# fat41.net
KiCad netlist of a schematic drawn in Altium Designer
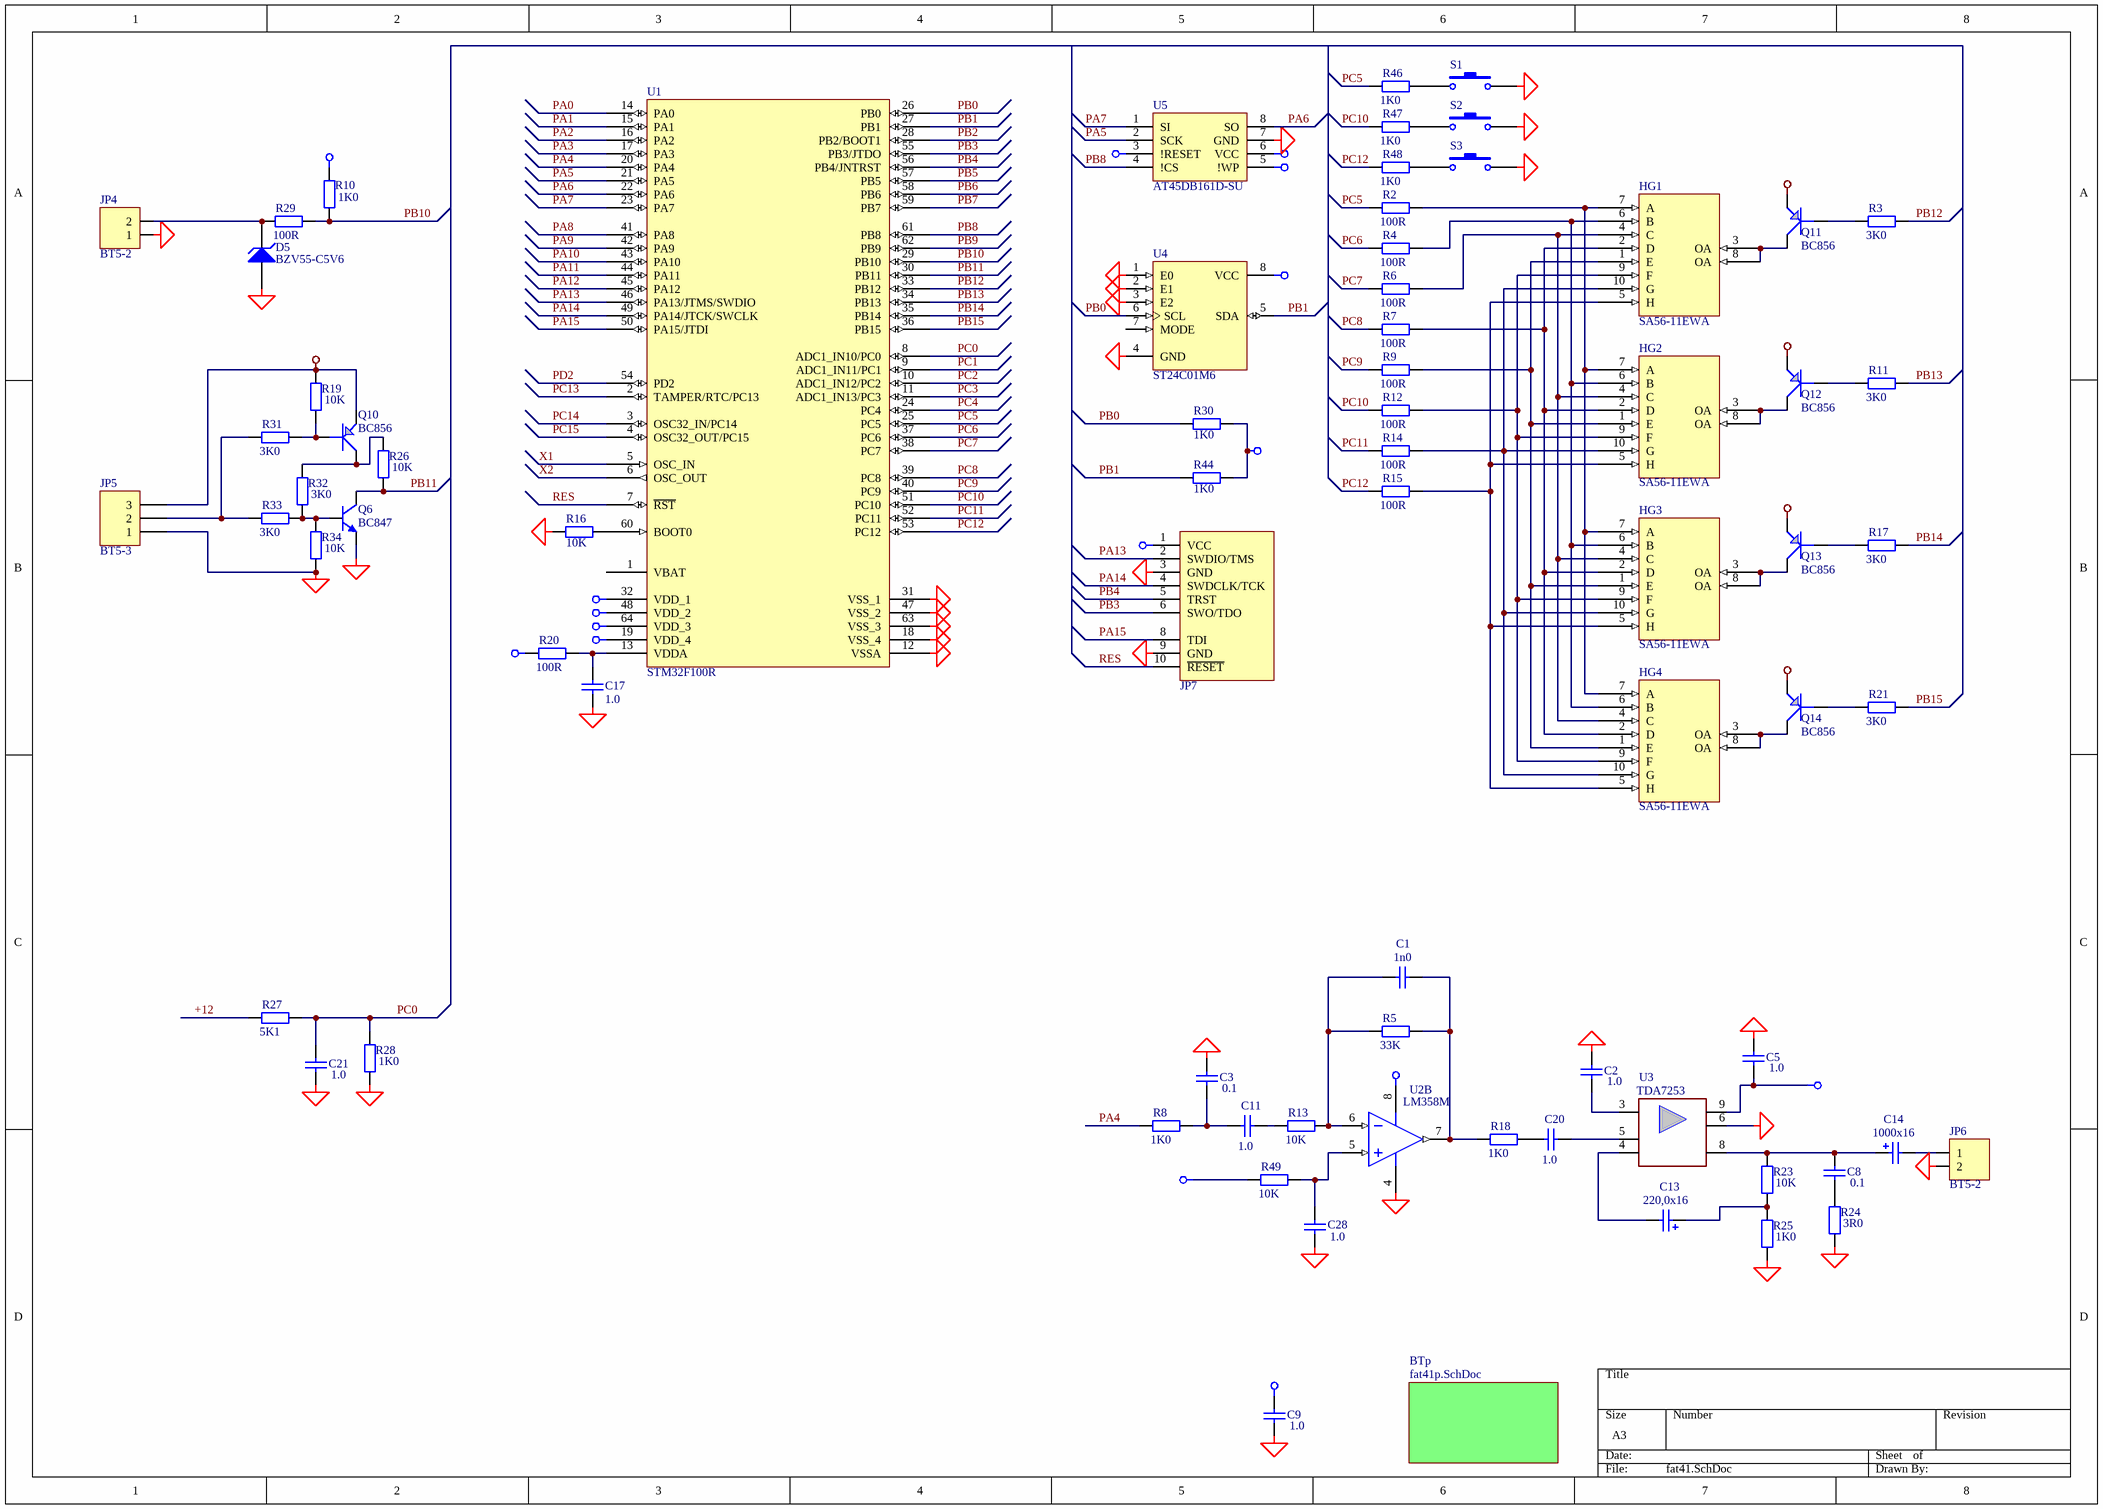
[diagram p0: fat41.SchDoc]

(export (version "E")
  (design (tool "Eeschema 10.0.6"))
  (components
    (comp (ref "C1")
      (value "1n0")
      (footprint "_1206")
      (description "Capacitor (Semiconductor SIM Model)")
      (fields (field (name "MANUFACTURER") "Generic Components") (field (name "PUBLISHER") "Altium Limited"))
      (libsource (lib "Miscellaneous Devices") (part "Cap Semi"))
    )
    (comp (ref "C2")
      (value "1.0")
      (footprint "C3216-1206")
      (description "Capacitor (Semiconductor SIM Model)")
      (fields (field (name "MANUFACTURER") "Generic Components") (field (name "PUBLISHER") "Altium Limited"))
      (libsource (lib "Miscellaneous Devices") (part "Cap Semi"))
    )
    (comp (ref "C3")
      (value "0.1")
      (footprint "_1206")
      (description "Capacitor (Semiconductor SIM Model)")
      (fields (field (name "MANUFACTURER") "Generic Components") (field (name "PUBLISHER") "Altium Limited"))
      (libsource (lib "") (part "Cap Semi_1"))
    )
    (comp (ref "C5")
      (value "1.0")
      (footprint "C3216-1206")
      (description "Capacitor (Semiconductor SIM Model)")
      (fields (field (name "MANUFACTURER") "Generic Components") (field (name "PUBLISHER") "Altium Limited"))
      (libsource (lib "Miscellaneous Devices") (part "Cap Semi"))
    )
    (comp (ref "C8")
      (value "0.1")
      (footprint "C3216-1206")
      (description "Capacitor (Semiconductor SIM Model)")
      (fields (field (name "MANUFACTURER") "Generic Components") (field (name "PUBLISHER") "Altium Limited"))
      (libsource (lib "Miscellaneous Devices") (part "Cap Semi"))
    )
    (comp (ref "C9")
      (value "1.0")
      (footprint "C3216-1206")
      (description "Capacitor (Semiconductor SIM Model)")
      (fields (field (name "MANUFACTURER") "Generic Components") (field (name "PUBLISHER") "Altium Limited"))
      (libsource (lib "Miscellaneous Devices") (part "Cap Semi"))
    )
    (comp (ref "C11")
      (value "1.0")
      (footprint "_1206")
      (description "Capacitor (Semiconductor SIM Model)")
      (fields (field (name "MANUFACTURER") "Generic Components") (field (name "PUBLISHER") "Altium Limited"))
      (libsource (lib "Miscellaneous Devices") (part "Cap Semi"))
    )
    (comp (ref "C13")
      (value "220,0x16")
      (footprint "el3")
      (description "Polarized Capacitor (Radial)")
      (fields (field (name "MANUFACTURER") "Generic Components") (field (name "PUBLISHER") "Altium Limited"))
      (libsource (lib "PAL") (part "Cap Pol1"))
    )
    (comp (ref "C14")
      (value "1000x16")
      (footprint "el5")
      (description "Polarized Capacitor (Radial)")
      (fields (field (name "MANUFACTURER") "Generic Components") (field (name "PUBLISHER") "Altium Limited"))
      (libsource (lib "PAL") (part "Cap Pol1"))
    )
    (comp (ref "C17")
      (value "1.0")
      (footprint "_1206")
      (description "Capacitor (Semiconductor SIM Model)")
      (fields (field (name "MANUFACTURER") "Generic Components") (field (name "PUBLISHER") "Altium Limited"))
      (libsource (lib "") (part "Cap Semi_1"))
    )
    (comp (ref "C20")
      (value "1.0")
      (footprint "_1206")
      (description "Capacitor (Semiconductor SIM Model)")
      (fields (field (name "MANUFACTURER") "Generic Components") (field (name "PUBLISHER") "Altium Limited"))
      (libsource (lib "Miscellaneous Devices") (part "Cap Semi"))
    )
    (comp (ref "C21")
      (value "1.0")
      (footprint "_1206")
      (description "Capacitor (Semiconductor SIM Model)")
      (fields (field (name "MANUFACTURER") "Generic Components") (field (name "PUBLISHER") "Altium Limited"))
      (libsource (lib "Miscellaneous Devices") (part "Cap Semi"))
    )
    (comp (ref "C28")
      (value "1.0")
      (footprint "_1206")
      (description "Capacitor (Semiconductor SIM Model)")
      (fields (field (name "MANUFACTURER") "Generic Components") (field (name "PUBLISHER") "Altium Limited"))
      (libsource (lib "") (part "Cap Semi_1"))
    )
    (comp (ref "D5")
      (value "BZV55-C5V6")
      (footprint "_1206d")
      (description "Zener Diode")
      (fields (field (name "MANUFACTURER") "Generic Components") (field (name "PUBLISHER") "Altium Limited"))
      (libsource (lib "Miscellaneous Devices") (part "D Zener"))
    )
    (comp (ref "HG1") (value "SA56-11EWA") (footprint "DIP10") (libsource (lib "PAL") (part "SA05")))
    (comp (ref "HG2") (value "SA56-11EWA") (footprint "DIP10") (libsource (lib "PAL") (part "SA05")))
    (comp (ref "HG3") (value "SA56-11EWA") (footprint "DIP10") (libsource (lib "PAL") (part "SA05")))
    (comp (ref "HG4") (value "SA56-11EWA") (footprint "DIP10") (libsource (lib "PAL") (part "SA05")))
    (comp (ref "JP4")
      (value "BT5-2")
      (footprint "BT5-2-1")
      (description "Header, 3-Pin")
      (fields (field (name "MANUFACTURER") "Generic Components") (field (name "PUBLISHER") "Altium Limited"))
      (libsource (lib "") (part "BT5-2_1"))
    )
    (comp (ref "JP5")
      (value "BT5-3")
      (footprint "BT5-3")
      (description "Header, 3-Pin")
      (fields (field (name "MANUFACTURER") "Generic Components") (field (name "PUBLISHER") "Altium Limited"))
      (libsource (lib "Miscellaneous Connectors") (part "Header 3"))
    )
    (comp (ref "JP6")
      (value "BT5-2")
      (footprint "BT5-2-1")
      (description "Header, 3-Pin")
      (fields (field (name "MANUFACTURER") "Generic Components") (field (name "PUBLISHER") "Altium Limited"))
      (libsource (lib "PAL") (part "BT5-2"))
    )
    (comp (ref "JP7")
      (value "CORTEX_DEBUG_CONNECTOR_PAL")
      (footprint "CORTEX_DEBUG_CONNECTOR")
      (libsource (lib "PAL") (part "CORTEX_DEBUG_CONNECTOR_PAL"))
    )
    (comp (ref "Q6")
      (value "BC847")
      (footprint "SO-G3")
      (description "General Purpose Transistor NPN Silicon")
      (fields (field (name "MANUFACTURER") "Motorola") (field (name "PUBLISHER") "Altium Limited"))
      (libsource (lib "PAL") (part "BC847ALT1"))
    )
    (comp (ref "Q10") (value "BC856") (footprint "SO-G3") (libsource (lib "MAIN") (part "GT109")))
    (comp (ref "Q11") (value "BC856") (footprint "SO-G3") (libsource (lib "MAIN") (part "GT109")))
    (comp (ref "Q12") (value "BC856") (footprint "SO-G3") (libsource (lib "MAIN") (part "GT109")))
    (comp (ref "Q13") (value "BC856") (footprint "SO-G3") (libsource (lib "MAIN") (part "GT109")))
    (comp (ref "Q14") (value "BC856") (footprint "SO-G3") (libsource (lib "MAIN") (part "GT109")))
    (comp (ref "R2")
      (value "100R")
      (footprint "_1206")
      (description "Resistor")
      (fields (field (name "MANUFACTURER") "Generic Components") (field (name "PUBLISHER") "Altium Limited"))
      (libsource (lib "PAL") (part "RES"))
    )
    (comp (ref "R3")
      (value "3K0")
      (footprint "_1206")
      (description "Resistor")
      (fields (field (name "MANUFACTURER") "Generic Components") (field (name "PUBLISHER") "Altium Limited"))
      (libsource (lib "PAL") (part "RES"))
    )
    (comp (ref "R4")
      (value "100R")
      (footprint "_1206")
      (description "Resistor")
      (fields (field (name "MANUFACTURER") "Generic Components") (field (name "PUBLISHER") "Altium Limited"))
      (libsource (lib "PAL") (part "RES"))
    )
    (comp (ref "R5")
      (value "33K")
      (footprint "_1206")
      (description "Resistor")
      (fields (field (name "MANUFACTURER") "Generic Components") (field (name "PUBLISHER") "Altium Limited"))
      (libsource (lib "") (part "Res2_1"))
    )
    (comp (ref "R6")
      (value "100R")
      (footprint "_1206")
      (description "Resistor")
      (fields (field (name "MANUFACTURER") "Generic Components") (field (name "PUBLISHER") "Altium Limited"))
      (libsource (lib "PAL") (part "RES"))
    )
    (comp (ref "R7")
      (value "100R")
      (footprint "_1206")
      (description "Resistor")
      (fields (field (name "MANUFACTURER") "Generic Components") (field (name "PUBLISHER") "Altium Limited"))
      (libsource (lib "PAL") (part "RES"))
    )
    (comp (ref "R8")
      (value "1K0")
      (footprint "_1206")
      (description "Resistor")
      (fields (field (name "MANUFACTURER") "Generic Components") (field (name "PUBLISHER") "Altium Limited"))
      (libsource (lib "") (part "Res2_1"))
    )
    (comp (ref "R9")
      (value "100R")
      (footprint "_1206")
      (description "Resistor")
      (fields (field (name "MANUFACTURER") "Generic Components") (field (name "PUBLISHER") "Altium Limited"))
      (libsource (lib "PAL") (part "RES"))
    )
    (comp (ref "R10")
      (value "1K0")
      (footprint "_1206")
      (description "Resistor")
      (fields (field (name "MANUFACTURER") "Generic Components") (field (name "PUBLISHER") "Altium Limited"))
      (libsource (lib "") (part "Res2_2"))
    )
    (comp (ref "R11")
      (value "3K0")
      (footprint "_1206")
      (description "Resistor")
      (fields (field (name "MANUFACTURER") "Generic Components") (field (name "PUBLISHER") "Altium Limited"))
      (libsource (lib "PAL") (part "RES"))
    )
    (comp (ref "R12")
      (value "100R")
      (footprint "_1206")
      (description "Resistor")
      (fields (field (name "MANUFACTURER") "Generic Components") (field (name "PUBLISHER") "Altium Limited"))
      (libsource (lib "PAL") (part "RES"))
    )
    (comp (ref "R13")
      (value "10K")
      (footprint "_1206")
      (description "Resistor")
      (fields (field (name "MANUFACTURER") "Generic Components") (field (name "PUBLISHER") "Altium Limited"))
      (libsource (lib "") (part "Res2_1"))
    )
    (comp (ref "R14")
      (value "100R")
      (footprint "_1206")
      (description "Resistor")
      (fields (field (name "MANUFACTURER") "Generic Components") (field (name "PUBLISHER") "Altium Limited"))
      (libsource (lib "PAL") (part "RES"))
    )
    (comp (ref "R15")
      (value "100R")
      (footprint "_1206")
      (description "Resistor")
      (fields (field (name "MANUFACTURER") "Generic Components") (field (name "PUBLISHER") "Altium Limited"))
      (libsource (lib "PAL") (part "RES"))
    )
    (comp (ref "R16")
      (value "10K")
      (footprint "_1206")
      (description "Resistor")
      (fields (field (name "MANUFACTURER") "Generic Components") (field (name "PUBLISHER") "Altium Limited"))
      (libsource (lib "PAL") (part "RES"))
    )
    (comp (ref "R17")
      (value "3K0")
      (footprint "_1206")
      (description "Resistor")
      (fields (field (name "MANUFACTURER") "Generic Components") (field (name "PUBLISHER") "Altium Limited"))
      (libsource (lib "PAL") (part "RES"))
    )
    (comp (ref "R18")
      (value "1K0")
      (footprint "_1206")
      (description "Resistor")
      (fields (field (name "MANUFACTURER") "Generic Components") (field (name "PUBLISHER") "Altium Limited"))
      (libsource (lib "") (part "Res2_3"))
    )
    (comp (ref "R19")
      (value "10K")
      (footprint "_1206")
      (description "Resistor")
      (fields (field (name "MANUFACTURER") "Generic Components") (field (name "PUBLISHER") "Altium Limited"))
      (libsource (lib "PAL") (part "RES"))
    )
    (comp (ref "R20")
      (value "100R")
      (footprint "_1206")
      (description "Resistor")
      (fields (field (name "MANUFACTURER") "Generic Components") (field (name "PUBLISHER") "Altium Limited"))
      (libsource (lib "Miscellaneous Devices") (part "Res2"))
    )
    (comp (ref "R21")
      (value "3K0")
      (footprint "_1206")
      (description "Resistor")
      (fields (field (name "MANUFACTURER") "Generic Components") (field (name "PUBLISHER") "Altium Limited"))
      (libsource (lib "PAL") (part "RES"))
    )
    (comp (ref "R23")
      (value "10K")
      (footprint "_1206")
      (description "Resistor")
      (fields (field (name "MANUFACTURER") "Generic Components") (field (name "PUBLISHER") "Altium Limited"))
      (libsource (lib "") (part "RES_1"))
    )
    (comp (ref "R24")
      (value "3R0")
      (footprint "_1206")
      (description "Resistor")
      (fields (field (name "MANUFACTURER") "Generic Components") (field (name "PUBLISHER") "Altium Limited"))
      (libsource (lib "") (part "RES_1"))
    )
    (comp (ref "R25")
      (value "1K0")
      (footprint "_1206")
      (description "Resistor")
      (fields (field (name "MANUFACTURER") "Generic Components") (field (name "PUBLISHER") "Altium Limited"))
      (libsource (lib "") (part "RES_1"))
    )
    (comp (ref "R26")
      (value "10K")
      (footprint "_1206")
      (description "Resistor")
      (fields (field (name "MANUFACTURER") "Generic Components") (field (name "PUBLISHER") "Altium Limited"))
      (libsource (lib "") (part "RES_2"))
    )
    (comp (ref "R27")
      (value "5K1")
      (footprint "_1206")
      (description "Resistor")
      (fields (field (name "MANUFACTURER") "Generic Components") (field (name "PUBLISHER") "Altium Limited"))
      (libsource (lib "Miscellaneous Devices") (part "Res2"))
    )
    (comp (ref "R28")
      (value "1K0")
      (footprint "_1206")
      (description "Resistor")
      (fields (field (name "MANUFACTURER") "Generic Components") (field (name "PUBLISHER") "Altium Limited"))
      (libsource (lib "") (part "Res2_2"))
    )
    (comp (ref "R29")
      (value "100R")
      (footprint "_1206")
      (description "Resistor")
      (fields (field (name "MANUFACTURER") "Generic Components") (field (name "PUBLISHER") "Altium Limited"))
      (libsource (lib "Miscellaneous Devices") (part "Res2"))
    )
    (comp (ref "R30")
      (value "1K0")
      (footprint "_1206")
      (description "Resistor")
      (fields (field (name "MANUFACTURER") "Generic Components") (field (name "PUBLISHER") "Altium Limited"))
      (libsource (lib "PAL") (part "RES"))
    )
    (comp (ref "R31")
      (value "3K0")
      (footprint "_1206")
      (description "Resistor")
      (fields (field (name "MANUFACTURER") "Generic Components") (field (name "PUBLISHER") "Altium Limited"))
      (libsource (lib "Miscellaneous Devices") (part "Res2"))
    )
    (comp (ref "R32")
      (value "3K0")
      (footprint "_1206")
      (description "Resistor")
      (fields (field (name "MANUFACTURER") "Generic Components") (field (name "PUBLISHER") "Altium Limited"))
      (libsource (lib "") (part "Res2_2"))
    )
    (comp (ref "R33")
      (value "3K0")
      (footprint "_1206")
      (description "Resistor")
      (fields (field (name "MANUFACTURER") "Generic Components") (field (name "PUBLISHER") "Altium Limited"))
      (libsource (lib "Miscellaneous Devices") (part "Res2"))
    )
    (comp (ref "R34")
      (value "10K")
      (footprint "_1206")
      (description "Resistor")
      (fields (field (name "MANUFACTURER") "Generic Components") (field (name "PUBLISHER") "Altium Limited"))
      (libsource (lib "") (part "Res2_1"))
    )
    (comp (ref "R44")
      (value "1K0")
      (footprint "_1206")
      (description "Resistor")
      (fields (field (name "MANUFACTURER") "Generic Components") (field (name "PUBLISHER") "Altium Limited"))
      (libsource (lib "PAL") (part "RES"))
    )
    (comp (ref "R46")
      (value "1K0")
      (footprint "_1206")
      (description "Resistor")
      (fields (field (name "MANUFACTURER") "Generic Components") (field (name "PUBLISHER") "Altium Limited"))
      (libsource (lib "PAL") (part "RES"))
    )
    (comp (ref "R47")
      (value "1K0")
      (footprint "_1206")
      (description "Resistor")
      (fields (field (name "MANUFACTURER") "Generic Components") (field (name "PUBLISHER") "Altium Limited"))
      (libsource (lib "PAL") (part "RES"))
    )
    (comp (ref "R48")
      (value "1K0")
      (footprint "_1206")
      (description "Resistor")
      (fields (field (name "MANUFACTURER") "Generic Components") (field (name "PUBLISHER") "Altium Limited"))
      (libsource (lib "PAL") (part "RES"))
    )
    (comp (ref "R49")
      (value "10K")
      (footprint "_1206")
      (description "Resistor")
      (fields (field (name "MANUFACTURER") "Generic Components") (field (name "PUBLISHER") "Altium Limited"))
      (libsource (lib "") (part "Res2_1"))
    )
    (comp (ref "S1")
      (value "SWT-6")
      (footprint "SWT-6-9")
      (description "Switch")
      (fields (field (name "MANUFACTURER") "Generic Components") (field (name "PUBLISHER") "Altium Limited"))
      (libsource (lib "PAL") (part "SWT-6"))
    )
    (comp (ref "S2")
      (value "SWT-6")
      (footprint "SWT-6-9")
      (description "Switch")
      (fields (field (name "MANUFACTURER") "Generic Components") (field (name "PUBLISHER") "Altium Limited"))
      (libsource (lib "PAL") (part "SWT-6"))
    )
    (comp (ref "S3")
      (value "SWT-6")
      (footprint "SWT-6-9")
      (description "Switch")
      (fields (field (name "MANUFACTURER") "Generic Components") (field (name "PUBLISHER") "Altium Limited"))
      (libsource (lib "PAL") (part "SWT-6"))
    )
    (comp (ref "U1")
      (value "STM32F100R")
      (footprint "F-QFP10X10-G64/N")
      (description "STM32 ARM-based 32-bit MCU with 64 Kbytes Flash, 64-pin LQFP, Industrial Temperature")
      (fields (field (name "PUBLISHER") "*"))
      (libsource (lib "PAL") (part "STM32F100R"))
    )
    (comp (ref "U2")
      (value "LM358M")
      (footprint "SO-G8")
      (description "Low-Power Dual Operational Amplifier")
      (fields
        (field (name "MANUFACTURER") "National Semiconductor")
        (field (name "PUBLISHER") "Altium Limited")
      )
      (libsource (lib "NSC Operational Amplifier") (part "LM358M"))
    )
    (comp (ref "U3") (value "TDA7253") (footprint "Clipwatt11") (libsource (lib "PAL") (part "TDA7253")))
    (comp (ref "U4")
      (value "ST24C01M6")
      (footprint "SO-G8")
      (description "Serial 1K (128 x 8) EEPROM")
      (fields (field (name "MANUFACTURER") "ST-Microelectronics") (field (name "PUBLISHER") "Altium Limited"))
      (libsource (lib "ST Memory EEPROM Serial") (part "ST24C01M6"))
    )
    (comp (ref "U5")
      (value "AT45DB161D-SU")
      (footprint "at45w")
      (libsource (lib "igorenja") (part "AT45DB161D-SU"))
    )
  )
  (nets
    (net (code "1") (name "+3v3") (class "Default")
      (node (ref "C9") (pin "2") (pinfunction "2_2") (pintype "passive"))
      (node (ref "JP7") (pin "1") (pinfunction "VCC_1") (pintype "passive"))
      (node (ref "Q11") (pin "2") (pinfunction "E_2") (pintype "passive"))
      (node (ref "Q12") (pin "2") (pinfunction "E_2") (pintype "passive"))
      (node (ref "Q13") (pin "2") (pinfunction "E_2") (pintype "passive"))
      (node (ref "Q14") (pin "2") (pinfunction "E_2") (pintype "passive"))
      (node (ref "R10") (pin "1") (pinfunction "1_1") (pintype "passive"))
      (node (ref "R20") (pin "2") (pinfunction "2_2") (pintype "passive"))
      (node (ref "R30") (pin "2") (pinfunction "2_2") (pintype "passive"))
      (node (ref "R44") (pin "2") (pinfunction "2_2") (pintype "passive"))
      (node (ref "R49") (pin "2") (pinfunction "2_2") (pintype "passive"))
      (node (ref "U1") (pin "19") (pinfunction "VDD_4_19") (pintype "power_in"))
      (node (ref "U1") (pin "32") (pinfunction "VDD_1_32") (pintype "power_in"))
      (node (ref "U1") (pin "48") (pinfunction "VDD_2_48") (pintype "power_in"))
      (node (ref "U1") (pin "64") (pinfunction "VDD_3_64") (pintype "power_in"))
      (node (ref "U4") (pin "8") (pinfunction "VCC_8") (pintype "power_in"))
      (node (ref "U5") (pin "3") (pinfunction "!RESET_3") (pintype "passive"))
      (node (ref "U5") (pin "5") (pinfunction "!WP_5") (pintype "passive"))
      (node (ref "U5") (pin "6") (pinfunction "VCC_6") (pintype "passive"))
    )
    (net (code "2") (name "+12v") (class "Default")
      (node (ref "C5") (pin "1") (pinfunction "1_1") (pintype "passive"))
      (node (ref "JP5") (pin "3") (pinfunction "3_3") (pintype "passive"))
      (node (ref "Q10") (pin "2") (pinfunction "E_2") (pintype "passive"))
      (node (ref "R19") (pin "2") (pinfunction "2_2") (pintype "passive"))
      (node (ref "U2") (pin "8") (pinfunction "V+_8") (pintype "power_in"))
      (node (ref "U3") (pin "9") (pintype "passive"))
    )
    (net (code "3") (name "/+12") (class "Default")
      (node (ref "R27") (pin "2") (pinfunction "2_2") (pintype "passive"))
    )
    (net (code "4") (name "/PA0") (class "Default")
      (node (ref "U1") (pin "14") (pinfunction "PA0_14") (pintype "bidirectional"))
    )
    (net (code "5") (name "/PA1") (class "Default")
      (node (ref "U1") (pin "15") (pinfunction "PA1_15") (pintype "bidirectional"))
    )
    (net (code "6") (name "/PA2") (class "Default")
      (node (ref "U1") (pin "16") (pinfunction "PA2_16") (pintype "bidirectional"))
    )
    (net (code "7") (name "/PA3") (class "Default")
      (node (ref "U1") (pin "17") (pinfunction "PA3_17") (pintype "bidirectional"))
    )
    (net (code "8") (name "/PA4") (class "Default")
      (node (ref "R8") (pin "2") (pinfunction "2_2") (pintype "passive"))
      (node (ref "U1") (pin "20") (pinfunction "PA4_20") (pintype "bidirectional"))
    )
    (net (code "9") (name "/PA5") (class "Default")
      (node (ref "U1") (pin "21") (pinfunction "PA5_21") (pintype "bidirectional"))
      (node (ref "U5") (pin "2") (pinfunction "SCK_2") (pintype "passive"))
    )
    (net (code "10") (name "/PA6") (class "Default")
      (node (ref "U1") (pin "22") (pinfunction "PA6_22") (pintype "bidirectional"))
      (node (ref "U5") (pin "8") (pinfunction "SO_8") (pintype "passive"))
    )
    (net (code "11") (name "/PA7") (class "Default")
      (node (ref "U1") (pin "23") (pinfunction "PA7_23") (pintype "bidirectional"))
      (node (ref "U5") (pin "1") (pinfunction "SI_1") (pintype "passive"))
    )
    (net (code "12") (name "/PA8") (class "Default")
      (node (ref "U1") (pin "41") (pinfunction "PA8_41") (pintype "bidirectional"))
    )
    (net (code "13") (name "/PA9") (class "Default")
      (node (ref "U1") (pin "42") (pinfunction "PA9_42") (pintype "bidirectional"))
    )
    (net (code "14") (name "/PA10") (class "Default")
      (node (ref "U1") (pin "43") (pinfunction "PA10_43") (pintype "bidirectional"))
    )
    (net (code "15") (name "/PA11") (class "Default")
      (node (ref "U1") (pin "44") (pinfunction "PA11_44") (pintype "bidirectional"))
    )
    (net (code "16") (name "/PA12") (class "Default")
      (node (ref "U1") (pin "45") (pinfunction "PA12_45") (pintype "bidirectional"))
    )
    (net (code "17") (name "/PA13") (class "Default")
      (node (ref "JP7") (pin "2") (pinfunction "SWDIO/TMS_2") (pintype "passive"))
      (node (ref "U1") (pin "46") (pinfunction "PA13/JTMS/SWDIO_46") (pintype "bidirectional"))
    )
    (net (code "18") (name "/PA14") (class "Default")
      (node (ref "JP7") (pin "4") (pinfunction "SWDCLK/TCK_4") (pintype "passive"))
      (node (ref "U1") (pin "49") (pinfunction "PA14/JTCK/SWCLK_49") (pintype "bidirectional"))
    )
    (net (code "19") (name "/PA15") (class "Default")
      (node (ref "JP7") (pin "8") (pinfunction "TDI_8") (pintype "passive"))
      (node (ref "U1") (pin "50") (pinfunction "PA15/JTDI_50") (pintype "bidirectional"))
    )
    (net (code "20") (name "/PB0") (class "Default")
      (node (ref "R30") (pin "1") (pinfunction "1_1") (pintype "passive"))
      (node (ref "U1") (pin "26") (pinfunction "PB0_26") (pintype "bidirectional"))
      (node (ref "U4") (pin "6") (pinfunction "SCL_6") (pintype "input"))
    )
    (net (code "21") (name "/PB1") (class "Default")
      (node (ref "R44") (pin "1") (pinfunction "1_1") (pintype "passive"))
      (node (ref "U1") (pin "27") (pinfunction "PB1_27") (pintype "bidirectional"))
      (node (ref "U4") (pin "5") (pinfunction "SDA_5") (pintype "bidirectional"))
    )
    (net (code "22") (name "/PB2") (class "Default")
      (node (ref "U1") (pin "28") (pinfunction "PB2/BOOT1_28") (pintype "bidirectional"))
    )
    (net (code "23") (name "/PB3") (class "Default")
      (node (ref "JP7") (pin "6") (pinfunction "SWO/TDO_6") (pintype "passive"))
      (node (ref "U1") (pin "55") (pinfunction "PB3/JTDO_55") (pintype "bidirectional"))
    )
    (net (code "24") (name "/PB4") (class "Default")
      (node (ref "JP7") (pin "5") (pinfunction "TRST_5") (pintype "passive"))
      (node (ref "U1") (pin "56") (pinfunction "PB4/JNTRST_56") (pintype "bidirectional"))
    )
    (net (code "25") (name "/PB5") (class "Default")
      (node (ref "U1") (pin "57") (pinfunction "PB5_57") (pintype "bidirectional"))
    )
    (net (code "26") (name "/PB6") (class "Default")
      (node (ref "U1") (pin "58") (pinfunction "PB6_58") (pintype "bidirectional"))
    )
    (net (code "27") (name "/PB7") (class "Default")
      (node (ref "U1") (pin "59") (pinfunction "PB7_59") (pintype "bidirectional"))
    )
    (net (code "28") (name "/PB8") (class "Default")
      (node (ref "U1") (pin "61") (pinfunction "PB8_61") (pintype "bidirectional"))
      (node (ref "U5") (pin "4") (pinfunction "!CS_4") (pintype "passive"))
    )
    (net (code "29") (name "/PB9") (class "Default")
      (node (ref "U1") (pin "62") (pinfunction "PB9_62") (pintype "bidirectional"))
    )
    (net (code "30") (name "/PB10") (class "Default")
      (node (ref "R10") (pin "2") (pinfunction "2_2") (pintype "passive"))
      (node (ref "R29") (pin "1") (pinfunction "1_1") (pintype "passive"))
      (node (ref "U1") (pin "29") (pinfunction "PB10_29") (pintype "bidirectional"))
    )
    (net (code "31") (name "/PB11") (class "Default")
      (node (ref "Q6") (pin "3") (pinfunction "C_3") (pintype "passive"))
      (node (ref "R26") (pin "2") (pinfunction "2_2") (pintype "passive"))
      (node (ref "U1") (pin "30") (pinfunction "PB11_30") (pintype "bidirectional"))
    )
    (net (code "32") (name "/PB12") (class "Default")
      (node (ref "R3") (pin "2") (pinfunction "2_2") (pintype "passive"))
      (node (ref "U1") (pin "33") (pinfunction "PB12_33") (pintype "bidirectional"))
    )
    (net (code "33") (name "/PB13") (class "Default")
      (node (ref "R11") (pin "2") (pinfunction "2_2") (pintype "passive"))
      (node (ref "U1") (pin "34") (pinfunction "PB13_34") (pintype "bidirectional"))
    )
    (net (code "34") (name "/PB14") (class "Default")
      (node (ref "R17") (pin "2") (pinfunction "2_2") (pintype "passive"))
      (node (ref "U1") (pin "35") (pinfunction "PB14_35") (pintype "bidirectional"))
    )
    (net (code "35") (name "/PB15") (class "Default")
      (node (ref "R21") (pin "2") (pinfunction "2_2") (pintype "passive"))
      (node (ref "U1") (pin "36") (pinfunction "PB15_36") (pintype "bidirectional"))
    )
    (net (code "36") (name "/PC0") (class "Default")
      (node (ref "C21") (pin "2") (pinfunction "2_2") (pintype "passive"))
      (node (ref "R27") (pin "1") (pinfunction "1_1") (pintype "passive"))
      (node (ref "R28") (pin "1") (pinfunction "1_1") (pintype "passive"))
      (node (ref "U1") (pin "8") (pinfunction "ADC1_IN10/PC0_8") (pintype "bidirectional"))
    )
    (net (code "37") (name "/PC1") (class "Default")
      (node (ref "U1") (pin "9") (pinfunction "ADC1_IN11/PC1_9") (pintype "bidirectional"))
    )
    (net (code "38") (name "/PC2") (class "Default")
      (node (ref "U1") (pin "10") (pinfunction "ADC1_IN12/PC2_10") (pintype "bidirectional"))
    )
    (net (code "39") (name "/PC3") (class "Default")
      (node (ref "U1") (pin "11") (pinfunction "ADC1_IN13/PC3_11") (pintype "bidirectional"))
    )
    (net (code "40") (name "/PC4") (class "Default")
      (node (ref "U1") (pin "24") (pinfunction "PC4_24") (pintype "bidirectional"))
    )
    (net (code "41") (name "/PC5") (class "Default")
      (node (ref "R2") (pin "1") (pinfunction "1_1") (pintype "passive"))
      (node (ref "R46") (pin "1") (pinfunction "1_1") (pintype "passive"))
      (node (ref "U1") (pin "25") (pinfunction "PC5_25") (pintype "bidirectional"))
    )
    (net (code "42") (name "/PC6") (class "Default")
      (node (ref "R4") (pin "1") (pinfunction "1_1") (pintype "passive"))
      (node (ref "U1") (pin "37") (pinfunction "PC6_37") (pintype "bidirectional"))
    )
    (net (code "43") (name "/PC7") (class "Default")
      (node (ref "R6") (pin "1") (pinfunction "1_1") (pintype "passive"))
      (node (ref "U1") (pin "38") (pinfunction "PC7_38") (pintype "bidirectional"))
    )
    (net (code "44") (name "/PC8") (class "Default")
      (node (ref "R7") (pin "1") (pinfunction "1_1") (pintype "passive"))
      (node (ref "U1") (pin "39") (pinfunction "PC8_39") (pintype "bidirectional"))
    )
    (net (code "45") (name "/PC9") (class "Default")
      (node (ref "R9") (pin "1") (pinfunction "1_1") (pintype "passive"))
      (node (ref "U1") (pin "40") (pinfunction "PC9_40") (pintype "bidirectional"))
    )
    (net (code "46") (name "/PC10") (class "Default")
      (node (ref "R12") (pin "1") (pinfunction "1_1") (pintype "passive"))
      (node (ref "R47") (pin "1") (pinfunction "1_1") (pintype "passive"))
      (node (ref "U1") (pin "51") (pinfunction "PC10_51") (pintype "bidirectional"))
    )
    (net (code "47") (name "/PC11") (class "Default")
      (node (ref "R14") (pin "1") (pinfunction "1_1") (pintype "passive"))
      (node (ref "U1") (pin "52") (pinfunction "PC11_52") (pintype "bidirectional"))
    )
    (net (code "48") (name "/PC12") (class "Default")
      (node (ref "R15") (pin "1") (pinfunction "1_1") (pintype "passive"))
      (node (ref "R48") (pin "1") (pinfunction "1_1") (pintype "passive"))
      (node (ref "U1") (pin "53") (pinfunction "PC12_53") (pintype "bidirectional"))
    )
    (net (code "49") (name "/PC13") (class "Default")
      (node (ref "U1") (pin "2") (pinfunction "TAMPER/RTC/PC13_2") (pintype "bidirectional"))
    )
    (net (code "50") (name "/PC14") (class "Default")
      (node (ref "U1") (pin "3") (pinfunction "OSC32_IN/PC14_3") (pintype "bidirectional"))
    )
    (net (code "51") (name "/PC15") (class "Default")
      (node (ref "U1") (pin "4") (pinfunction "OSC32_OUT/PC15_4") (pintype "bidirectional"))
    )
    (net (code "52") (name "/PD2") (class "Default")
      (node (ref "U1") (pin "54") (pinfunction "PD2_54") (pintype "bidirectional"))
    )
    (net (code "53") (name "/RES") (class "Default")
      (node (ref "JP7") (pin "10") (pinfunction "~{RESET}_10") (pintype "passive"))
      (node (ref "U1") (pin "7") (pinfunction "~{RST}_7") (pintype "bidirectional"))
    )
    (net (code "54") (name "/X1") (class "Default")
      (node (ref "U1") (pin "5") (pinfunction "OSC_IN_5") (pintype "input"))
    )
    (net (code "55") (name "/X2") (class "Default")
      (node (ref "U1") (pin "6") (pinfunction "OSC_OUT_6") (pintype "output"))
    )
    (net (code "56") (name "GND") (class "Default")
      (node (ref "C17") (pin "2") (pinfunction "2_2") (pintype "passive"))
      (node (ref "C2") (pin "2") (pinfunction "2_2") (pintype "passive"))
      (node (ref "C21") (pin "1") (pinfunction "1_1") (pintype "passive"))
      (node (ref "C28") (pin "2") (pinfunction "2_2") (pintype "passive"))
      (node (ref "C3") (pin "2") (pinfunction "2_2") (pintype "passive"))
      (node (ref "C5") (pin "2") (pinfunction "2_2") (pintype "passive"))
      (node (ref "C9") (pin "1") (pinfunction "1_1") (pintype "passive"))
      (node (ref "D5") (pin "1") (pinfunction "A_1") (pintype "passive"))
      (node (ref "JP4") (pin "1") (pinfunction "1_1") (pintype "passive"))
      (node (ref "JP5") (pin "1") (pinfunction "1_1") (pintype "passive"))
      (node (ref "JP6") (pin "2") (pinfunction "2_2") (pintype "passive"))
      (node (ref "JP7") (pin "3") (pinfunction "GND_3") (pintype "passive"))
      (node (ref "JP7") (pin "9") (pinfunction "GND_9") (pintype "passive"))
      (node (ref "Q6") (pin "2") (pinfunction "E_2") (pintype "passive"))
      (node (ref "R16") (pin "1") (pinfunction "1_1") (pintype "passive"))
      (node (ref "R24") (pin "1") (pinfunction "1_1") (pintype "passive"))
      (node (ref "R25") (pin "1") (pinfunction "1_1") (pintype "passive"))
      (node (ref "R28") (pin "2") (pinfunction "2_2") (pintype "passive"))
      (node (ref "R34") (pin "2") (pinfunction "2_2") (pintype "passive"))
      (node (ref "S1") (pin "2") (pinfunction "2_2") (pintype "passive"))
      (node (ref "S2") (pin "2") (pinfunction "2_2") (pintype "passive"))
      (node (ref "S3") (pin "2") (pinfunction "2_2") (pintype "passive"))
      (node (ref "U1") (pin "12") (pinfunction "VSSA_12") (pintype "power_in"))
      (node (ref "U1") (pin "18") (pinfunction "VSS_4_18") (pintype "power_in"))
      (node (ref "U1") (pin "31") (pinfunction "VSS_1_31") (pintype "power_in"))
      (node (ref "U1") (pin "47") (pinfunction "VSS_2_47") (pintype "power_in"))
      (node (ref "U1") (pin "63") (pinfunction "VSS_3_63") (pintype "power_in"))
      (node (ref "U2") (pin "4") (pinfunction "GND_4") (pintype "power_in"))
      (node (ref "U3") (pin "6") (pintype "passive"))
      (node (ref "U4") (pin "1") (pinfunction "E0_1") (pintype "input"))
      (node (ref "U4") (pin "2") (pinfunction "E1_2") (pintype "input"))
      (node (ref "U4") (pin "3") (pinfunction "E2_3") (pintype "input"))
      (node (ref "U4") (pin "4") (pinfunction "GND_4") (pintype "power_in"))
      (node (ref "U5") (pin "7") (pinfunction "GND_7") (pintype "passive"))
    )
    (net (code "57") (name "Net-(C8-Pad1)") (class "Default")
      (node (ref "C8") (pin "1") (pinfunction "1_1") (pintype "passive"))
      (node (ref "R24") (pin "2") (pinfunction "2_2") (pintype "passive"))
    )
    (net (code "58") (name "Net-(C11-Pad1)") (class "Default")
      (node (ref "C11") (pin "1") (pinfunction "1_1") (pintype "passive"))
      (node (ref "C3") (pin "1") (pinfunction "1_1") (pintype "passive"))
      (node (ref "R8") (pin "1") (pinfunction "1_1") (pintype "passive"))
    )
    (net (code "59") (name "Net-(C11-Pad2)") (class "Default")
      (node (ref "C11") (pin "2") (pinfunction "2_2") (pintype "passive"))
      (node (ref "R13") (pin "2") (pinfunction "2_2") (pintype "passive"))
    )
    (net (code "60") (name "Net-(C13-Pad1)") (class "Default")
      (node (ref "C13") (pin "1") (pinfunction "1_1") (pintype "passive"))
      (node (ref "R23") (pin "1") (pinfunction "1_1") (pintype "passive"))
      (node (ref "R25") (pin "2") (pinfunction "2_2") (pintype "passive"))
    )
    (net (code "61") (name "Net-(C13-Pad2)") (class "Default")
      (node (ref "C13") (pin "2") (pinfunction "2_2") (pintype "passive"))
      (node (ref "U3") (pin "4") (pintype "passive"))
    )
    (net (code "62") (name "Net-(C14-Pad1)") (class "Default")
      (node (ref "C14") (pin "1") (pinfunction "1_1") (pintype "passive"))
      (node (ref "C8") (pin "2") (pinfunction "2_2") (pintype "passive"))
      (node (ref "R23") (pin "2") (pinfunction "2_2") (pintype "passive"))
      (node (ref "U3") (pin "8") (pintype "passive"))
    )
    (net (code "63") (name "Net-(C14-Pad2)") (class "Default")
      (node (ref "C14") (pin "2") (pinfunction "2_2") (pintype "passive"))
      (node (ref "JP6") (pin "1") (pinfunction "1_1") (pintype "passive"))
    )
    (net (code "64") (name "Net-(C20-Pad1)") (class "Default")
      (node (ref "C20") (pin "1") (pinfunction "1_1") (pintype "passive"))
      (node (ref "R18") (pin "2") (pinfunction "2_2") (pintype "passive"))
    )
    (net (code "65") (name "Net-(D5-K)") (class "Default")
      (node (ref "D5") (pin "2") (pinfunction "K_2") (pintype "passive"))
      (node (ref "JP4") (pin "2") (pinfunction "2_2") (pintype "passive"))
      (node (ref "R29") (pin "2") (pinfunction "2_2") (pintype "passive"))
    )
    (net (code "66") (name "Net-(HG1-A)") (class "Default")
      (node (ref "HG1") (pin "7") (pinfunction "A_7") (pintype "input"))
      (node (ref "HG2") (pin "7") (pinfunction "A_7") (pintype "input"))
      (node (ref "HG3") (pin "7") (pinfunction "A_7") (pintype "input"))
      (node (ref "HG4") (pin "7") (pinfunction "A_7") (pintype "input"))
      (node (ref "R2") (pin "2") (pinfunction "2_2") (pintype "passive"))
    )
    (net (code "67") (name "Net-(HG1-B)") (class "Default")
      (node (ref "HG1") (pin "6") (pinfunction "B_6") (pintype "input"))
      (node (ref "HG2") (pin "6") (pinfunction "B_6") (pintype "input"))
      (node (ref "HG3") (pin "6") (pinfunction "B_6") (pintype "input"))
      (node (ref "HG4") (pin "6") (pinfunction "B_6") (pintype "input"))
      (node (ref "R4") (pin "2") (pinfunction "2_2") (pintype "passive"))
    )
    (net (code "68") (name "Net-(HG1-C)") (class "Default")
      (node (ref "HG1") (pin "4") (pinfunction "C_4") (pintype "input"))
      (node (ref "HG2") (pin "4") (pinfunction "C_4") (pintype "input"))
      (node (ref "HG3") (pin "4") (pinfunction "C_4") (pintype "input"))
      (node (ref "HG4") (pin "4") (pinfunction "C_4") (pintype "input"))
      (node (ref "R6") (pin "2") (pinfunction "2_2") (pintype "passive"))
    )
    (net (code "69") (name "Net-(HG1-D)") (class "Default")
      (node (ref "HG1") (pin "2") (pinfunction "D_2") (pintype "input"))
      (node (ref "HG2") (pin "2") (pinfunction "D_2") (pintype "input"))
      (node (ref "HG3") (pin "2") (pinfunction "D_2") (pintype "input"))
      (node (ref "HG4") (pin "2") (pinfunction "D_2") (pintype "input"))
      (node (ref "R7") (pin "2") (pinfunction "2_2") (pintype "passive"))
    )
    (net (code "70") (name "Net-(HG1-E)") (class "Default")
      (node (ref "HG1") (pin "1") (pinfunction "E_1") (pintype "input"))
      (node (ref "HG2") (pin "1") (pinfunction "E_1") (pintype "input"))
      (node (ref "HG3") (pin "1") (pinfunction "E_1") (pintype "input"))
      (node (ref "HG4") (pin "1") (pinfunction "E_1") (pintype "input"))
      (node (ref "R9") (pin "2") (pinfunction "2_2") (pintype "passive"))
    )
    (net (code "71") (name "Net-(HG1-F)") (class "Default")
      (node (ref "HG1") (pin "9") (pinfunction "F_9") (pintype "input"))
      (node (ref "HG2") (pin "9") (pinfunction "F_9") (pintype "input"))
      (node (ref "HG3") (pin "9") (pinfunction "F_9") (pintype "input"))
      (node (ref "HG4") (pin "9") (pinfunction "F_9") (pintype "input"))
      (node (ref "R12") (pin "2") (pinfunction "2_2") (pintype "passive"))
    )
    (net (code "72") (name "Net-(HG1-G)") (class "Default")
      (node (ref "HG1") (pin "10") (pinfunction "G_10") (pintype "input"))
      (node (ref "HG2") (pin "10") (pinfunction "G_10") (pintype "input"))
      (node (ref "HG3") (pin "10") (pinfunction "G_10") (pintype "input"))
      (node (ref "HG4") (pin "10") (pinfunction "G_10") (pintype "input"))
      (node (ref "R14") (pin "2") (pinfunction "2_2") (pintype "passive"))
    )
    (net (code "73") (name "Net-(HG1-H)") (class "Default")
      (node (ref "HG1") (pin "5") (pinfunction "H_5") (pintype "input"))
      (node (ref "HG2") (pin "5") (pinfunction "H_5") (pintype "input"))
      (node (ref "HG3") (pin "5") (pinfunction "H_5") (pintype "input"))
      (node (ref "HG4") (pin "5") (pinfunction "H_5") (pintype "input"))
      (node (ref "R15") (pin "2") (pinfunction "2_2") (pintype "passive"))
    )
    (net (code "74") (name "Net-(JP5-Pad2)") (class "Default")
      (node (ref "JP5") (pin "2") (pinfunction "2_2") (pintype "passive"))
      (node (ref "R31") (pin "2") (pinfunction "2_2") (pintype "passive"))
      (node (ref "R33") (pin "2") (pinfunction "2_2") (pintype "passive"))
    )
    (net (code "75") (name "Net-(Q6-B)") (class "Default")
      (node (ref "Q6") (pin "1") (pinfunction "B_1") (pintype "passive"))
      (node (ref "R32") (pin "2") (pinfunction "2_2") (pintype "passive"))
      (node (ref "R33") (pin "1") (pinfunction "1_1") (pintype "passive"))
      (node (ref "R34") (pin "1") (pinfunction "1_1") (pintype "passive"))
    )
    (net (code "76") (name "Net-(Q10-B)") (class "Default")
      (node (ref "Q10") (pin "1") (pinfunction "B_1") (pintype "passive"))
      (node (ref "R19") (pin "1") (pinfunction "1_1") (pintype "passive"))
      (node (ref "R31") (pin "1") (pinfunction "1_1") (pintype "passive"))
    )
    (net (code "77") (name "Net-(Q10-C)") (class "Default")
      (node (ref "Q10") (pin "3") (pinfunction "C_3") (pintype "passive"))
      (node (ref "R26") (pin "1") (pinfunction "1_1") (pintype "passive"))
      (node (ref "R32") (pin "1") (pinfunction "1_1") (pintype "passive"))
    )
    (net (code "78") (name "Net-(Q11-B)") (class "Default")
      (node (ref "Q11") (pin "1") (pinfunction "B_1") (pintype "passive"))
      (node (ref "R3") (pin "1") (pinfunction "1_1") (pintype "passive"))
    )
    (net (code "79") (name "Net-(Q11-C)") (class "Default")
      (node (ref "HG1") (pin "3") (pinfunction "OA_3") (pintype "input"))
      (node (ref "HG1") (pin "8") (pinfunction "OA_8") (pintype "input"))
      (node (ref "Q11") (pin "3") (pinfunction "C_3") (pintype "passive"))
    )
    (net (code "80") (name "Net-(Q12-B)") (class "Default")
      (node (ref "Q12") (pin "1") (pinfunction "B_1") (pintype "passive"))
      (node (ref "R11") (pin "1") (pinfunction "1_1") (pintype "passive"))
    )
    (net (code "81") (name "Net-(Q12-C)") (class "Default")
      (node (ref "HG2") (pin "3") (pinfunction "OA_3") (pintype "input"))
      (node (ref "HG2") (pin "8") (pinfunction "OA_8") (pintype "input"))
      (node (ref "Q12") (pin "3") (pinfunction "C_3") (pintype "passive"))
    )
    (net (code "82") (name "Net-(Q13-B)") (class "Default")
      (node (ref "Q13") (pin "1") (pinfunction "B_1") (pintype "passive"))
      (node (ref "R17") (pin "1") (pinfunction "1_1") (pintype "passive"))
    )
    (net (code "83") (name "Net-(Q13-C)") (class "Default")
      (node (ref "HG3") (pin "3") (pinfunction "OA_3") (pintype "input"))
      (node (ref "HG3") (pin "8") (pinfunction "OA_8") (pintype "input"))
      (node (ref "Q13") (pin "3") (pinfunction "C_3") (pintype "passive"))
    )
    (net (code "84") (name "Net-(Q14-B)") (class "Default")
      (node (ref "Q14") (pin "1") (pinfunction "B_1") (pintype "passive"))
      (node (ref "R21") (pin "1") (pinfunction "1_1") (pintype "passive"))
    )
    (net (code "85") (name "Net-(Q14-C)") (class "Default")
      (node (ref "HG4") (pin "3") (pinfunction "OA_3") (pintype "input"))
      (node (ref "HG4") (pin "8") (pinfunction "OA_8") (pintype "input"))
      (node (ref "Q14") (pin "3") (pinfunction "C_3") (pintype "passive"))
    )
    (net (code "86") (name "Net-(R46-Pad2)") (class "Default")
      (node (ref "R46") (pin "2") (pinfunction "2_2") (pintype "passive"))
      (node (ref "S1") (pin "1") (pinfunction "1_1") (pintype "passive"))
    )
    (net (code "87") (name "Net-(R47-Pad2)") (class "Default")
      (node (ref "R47") (pin "2") (pinfunction "2_2") (pintype "passive"))
      (node (ref "S2") (pin "1") (pinfunction "1_1") (pintype "passive"))
    )
    (net (code "88") (name "Net-(R48-Pad2)") (class "Default")
      (node (ref "R48") (pin "2") (pinfunction "2_2") (pintype "passive"))
      (node (ref "S3") (pin "1") (pinfunction "1_1") (pintype "passive"))
    )
    (net (code "89") (name "Net-(U1-BOOT0)") (class "Default")
      (node (ref "R16") (pin "2") (pinfunction "2_2") (pintype "passive"))
      (node (ref "U1") (pin "60") (pinfunction "BOOT0_60") (pintype "input"))
    )
    (net (code "90") (name "Net-(U1-VDDA)") (class "Default")
      (node (ref "C17") (pin "1") (pinfunction "1_1") (pintype "passive"))
      (node (ref "R20") (pin "1") (pinfunction "1_1") (pintype "passive"))
      (node (ref "U1") (pin "13") (pinfunction "VDDA_13") (pintype "power_in"))
    )
    (net (code "91") (name "Net-(U2B-IN+)") (class "Default")
      (node (ref "C28") (pin "1") (pinfunction "1_1") (pintype "passive"))
      (node (ref "R49") (pin "1") (pinfunction "1_1") (pintype "passive"))
      (node (ref "U2") (pin "5") (pinfunction "IN+_5") (pintype "input"))
    )
    (net (code "92") (name "Net-(U2B-IN-)") (class "Default")
      (node (ref "C1") (pin "2") (pinfunction "2_2") (pintype "passive"))
      (node (ref "R13") (pin "1") (pinfunction "1_1") (pintype "passive"))
      (node (ref "R5") (pin "2") (pinfunction "2_2") (pintype "passive"))
      (node (ref "U2") (pin "6") (pinfunction "IN-_6") (pintype "input"))
    )
    (net (code "93") (name "Net-(U2B-OUT)") (class "Default")
      (node (ref "C1") (pin "1") (pinfunction "1_1") (pintype "passive"))
      (node (ref "R18") (pin "1") (pinfunction "1_1") (pintype "passive"))
      (node (ref "R5") (pin "1") (pinfunction "1_1") (pintype "passive"))
      (node (ref "U2") (pin "7") (pinfunction "OUT_7") (pintype "output"))
    )
    (net (code "94") (name "Net-(U3-+)") (class "Default")
      (node (ref "C20") (pin "2") (pinfunction "2_2") (pintype "passive"))
      (node (ref "U3") (pin "5") (pinfunction "+_5") (pintype "passive"))
    )
    (net (code "95") (name "Net-(U3-MUTE)") (class "Default")
      (node (ref "C2") (pin "1") (pinfunction "1_1") (pintype "passive"))
      (node (ref "U3") (pin "3") (pinfunction "MUTE_3") (pintype "passive"))
    )
    (net (code "96") (name "unconnected-(U1-VBAT-Pad1)") (class "Default")
      (node (ref "U1") (pin "1") (pinfunction "VBAT_1") (pintype "power_in"))
    )
    (net (code "97") (name "unconnected-(U4-MODE-Pad7)") (class "Default")
      (node (ref "U4") (pin "7") (pinfunction "MODE_7") (pintype "input"))
    )
  )
)
